# workshop-atmega8.net
KiCad netlist of a schematic drawn in EAGLE
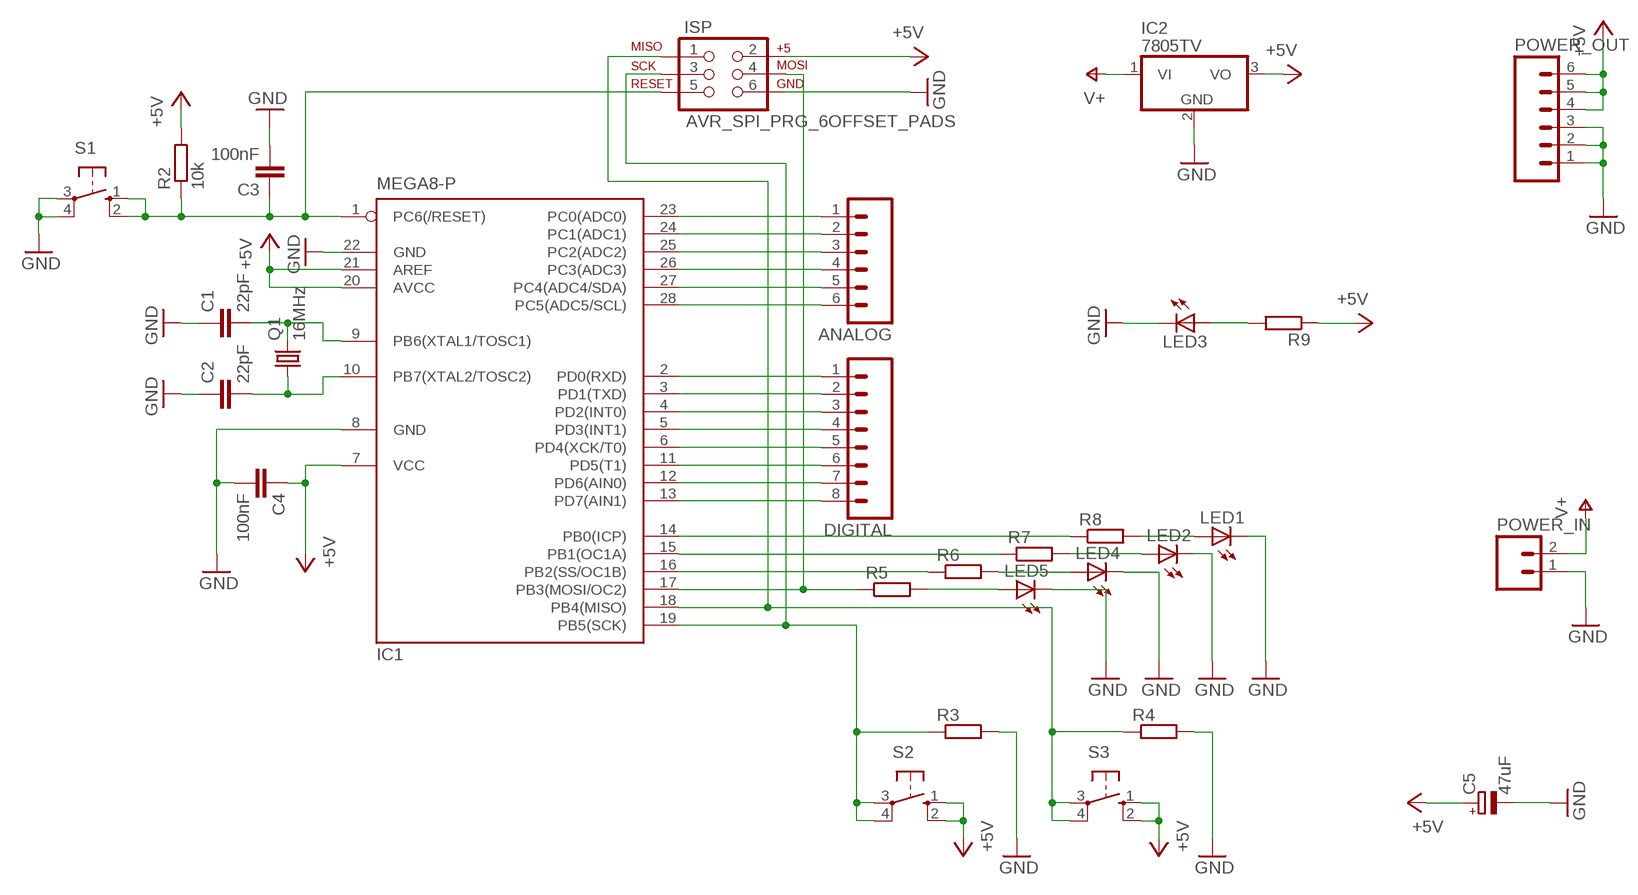
[diagram p0: schematic, sheet 1]

(export (version "E")
  (design (tool "Eeschema 10.0.6"))
  (components
    (comp (ref "ANALOG")
      (value "M06LOCK_LONGPADS")
      (footprint "eagle-import:1X06_LOCK_LONGPADS")
      (libsource (lib "eagle-import") (part "M06LOCK_LONGPADS"))
    )
    (comp (ref "C1")
      (value "22pF")
      (footprint "eagle-import:C025-025X050")
      (libsource (lib "eagle-import") (part "C-EU025-025X050"))
    )
    (comp (ref "C2")
      (value "22pF")
      (footprint "eagle-import:C025-025X050")
      (libsource (lib "eagle-import") (part "C-EU025-025X050"))
    )
    (comp (ref "C3")
      (value "100nF")
      (footprint "eagle-import:C025-025X050")
      (libsource (lib "eagle-import") (part "C-EU025-025X050"))
    )
    (comp (ref "C4")
      (value "100nF")
      (footprint "eagle-import:C025-025X050")
      (libsource (lib "eagle-import") (part "C-EU025-025X050"))
    )
    (comp (ref "C5")
      (value "47uF")
      (footprint "eagle-import:E2,5-7")
      (libsource (lib "eagle-import") (part "CPOL-EUE2.5-7"))
    )
    (comp (ref "DIGITAL")
      (value "M08LOCK_LONGPADS")
      (footprint "eagle-import:1X08_LOCK_LONGPADS")
      (libsource (lib "eagle-import") (part "M08LOCK_LONGPADS"))
    )
    (comp (ref "IC1")
      (value "MEGA8-P")
      (footprint "eagle-import:DIL28-3")
      (libsource (lib "eagle-import") (part "MEGA8-P"))
    )
    (comp (ref "IC2")
      (value "7805TV")
      (footprint "eagle-import:TO220V")
      (libsource (lib "eagle-import") (part "78TV05"))
    )
    (comp (ref "ISP")
      (value "AVR_SPI_PRG_6OFFSET_PADS")
      (footprint "eagle-import:2X3_OFFSET")
      (libsource (lib "eagle-import") (part "AVR_SPI_PRG_6OFFSET_PADS"))
    )
    (comp (ref "LED1")
      (value "LED5MM")
      (footprint "eagle-import:LED5MM")
      (libsource (lib "eagle-import") (part "LED5MM"))
    )
    (comp (ref "LED2")
      (value "LED5MM")
      (footprint "eagle-import:LED5MM")
      (libsource (lib "eagle-import") (part "LED5MM"))
    )
    (comp (ref "LED3")
      (value "LED5MM")
      (footprint "eagle-import:LED5MM")
      (libsource (lib "eagle-import") (part "LED5MM"))
    )
    (comp (ref "LED4")
      (value "LED5MM")
      (footprint "eagle-import:LED5MM")
      (libsource (lib "eagle-import") (part "LED5MM"))
    )
    (comp (ref "LED5")
      (value "LED5MM")
      (footprint "eagle-import:LED5MM")
      (libsource (lib "eagle-import") (part "LED5MM"))
    )
    (comp (ref "POWER_IN")
      (value "M02LOCK_LONGPADS")
      (footprint "eagle-import:1X02_LOCK_LONGPADS")
      (libsource (lib "eagle-import") (part "M02LOCK_LONGPADS"))
    )
    (comp (ref "POWER_OUT")
      (value "M06LOCK_LONGPADS")
      (footprint "eagle-import:1X06_LOCK_LONGPADS")
      (libsource (lib "eagle-import") (part "M06LOCK_LONGPADS"))
    )
    (comp (ref "Q1")
      (value "16MHz")
      (footprint "eagle-import:HC49_S")
      (libsource (lib "eagle-import") (part "CRYSTALHC49S"))
    )
    (comp (ref "R2")
      (value "10k")
      (footprint "eagle-import:0207_10")
      (libsource (lib "eagle-import") (part "R-EU_0207/10"))
    )
    (comp (ref "R3")
      (value "R-EU_0207/10")
      (footprint "eagle-import:0207_10")
      (libsource (lib "eagle-import") (part "R-EU_0207/10"))
    )
    (comp (ref "R4")
      (value "R-EU_0207/10")
      (footprint "eagle-import:0207_10")
      (libsource (lib "eagle-import") (part "R-EU_0207/10"))
    )
    (comp (ref "R5")
      (value "R-EU_0207/10")
      (footprint "eagle-import:0207_10")
      (libsource (lib "eagle-import") (part "R-EU_0207/10"))
    )
    (comp (ref "R6")
      (value "R-EU_0207/10")
      (footprint "eagle-import:0207_10")
      (libsource (lib "eagle-import") (part "R-EU_0207/10"))
    )
    (comp (ref "R7")
      (value "R-EU_0207/10")
      (footprint "eagle-import:0207_10")
      (libsource (lib "eagle-import") (part "R-EU_0207/10"))
    )
    (comp (ref "R8")
      (value "R-EU_0207/10")
      (footprint "eagle-import:0207_10")
      (libsource (lib "eagle-import") (part "R-EU_0207/10"))
    )
    (comp (ref "R9")
      (value "R-EU_0207/10")
      (footprint "eagle-import:0207_10")
      (libsource (lib "eagle-import") (part "R-EU_0207/10"))
    )
    (comp (ref "S1")
      (value "10-XX")
      (footprint "eagle-import:B3F-10XX")
      (fields (field (name "MPN") "B3F-1000"))
      (libsource (lib "eagle-import") (part "10-XX"))
    )
    (comp (ref "S2")
      (value "10-XX")
      (footprint "eagle-import:B3F-10XX")
      (fields (field (name "MPN") "B3F-1000"))
      (libsource (lib "eagle-import") (part "10-XX"))
    )
    (comp (ref "S3")
      (value "10-XX")
      (footprint "eagle-import:B3F-10XX")
      (fields (field (name "MPN") "B3F-1000"))
      (libsource (lib "eagle-import") (part "10-XX"))
    )
  )
  (nets
    (net (code "1") (name "+5V") (class "Default")
      (node (ref "C4") (pin "1") (pinfunction "1_1") (pintype "passive"))
      (node (ref "C5") (pin "+") (pinfunction "+_+") (pintype "passive"))
      (node (ref "IC1") (pin "20") (pinfunction "AVCC_20") (pintype "power_in"))
      (node (ref "IC1") (pin "21") (pinfunction "AREF_21") (pintype "passive"))
      (node (ref "IC1") (pin "7") (pinfunction "VCC_7") (pintype "power_in"))
      (node (ref "IC2") (pin "3") (pinfunction "VO_3") (pintype "passive"))
      (node (ref "ISP") (pin "2") (pinfunction "2_2") (pintype "passive"))
      (node (ref "POWER_OUT") (pin "4") (pinfunction "4_4") (pintype "passive"))
      (node (ref "POWER_OUT") (pin "5") (pinfunction "5_5") (pintype "passive"))
      (node (ref "POWER_OUT") (pin "6") (pinfunction "6_6") (pintype "passive"))
      (node (ref "R2") (pin "2") (pinfunction "2_2") (pintype "passive"))
      (node (ref "R9") (pin "1") (pinfunction "1_1") (pintype "passive"))
      (node (ref "S2") (pin "1") (pinfunction "S_1") (pintype "passive"))
      (node (ref "S2") (pin "2") (pinfunction "S1_2") (pintype "passive"))
      (node (ref "S3") (pin "1") (pinfunction "S_1") (pintype "passive"))
      (node (ref "S3") (pin "2") (pinfunction "S1_2") (pintype "passive"))
    )
    (net (code "2") (name "GND") (class "Default")
      (node (ref "C1") (pin "1") (pinfunction "1_1") (pintype "passive"))
      (node (ref "C2") (pin "1") (pinfunction "1_1") (pintype "passive"))
      (node (ref "C3") (pin "2") (pinfunction "2_2") (pintype "passive"))
      (node (ref "C4") (pin "2") (pinfunction "2_2") (pintype "passive"))
      (node (ref "C5") (pin "-") (pinfunction "-_-") (pintype "passive"))
      (node (ref "IC1") (pin "22") (pinfunction "GND_22") (pintype "power_in"))
      (node (ref "IC1") (pin "8") (pinfunction "GND_8") (pintype "power_in"))
      (node (ref "IC2") (pin "2") (pinfunction "GND_2") (pintype "passive"))
      (node (ref "ISP") (pin "6") (pinfunction "6_6") (pintype "passive"))
      (node (ref "LED1") (pin "K") (pinfunction "C_K") (pintype "passive"))
      (node (ref "LED2") (pin "K") (pinfunction "C_K") (pintype "passive"))
      (node (ref "LED3") (pin "K") (pinfunction "C_K") (pintype "passive"))
      (node (ref "LED4") (pin "K") (pinfunction "C_K") (pintype "passive"))
      (node (ref "LED5") (pin "K") (pinfunction "C_K") (pintype "passive"))
      (node (ref "POWER_IN") (pin "1") (pinfunction "1_1") (pintype "passive"))
      (node (ref "POWER_OUT") (pin "1") (pinfunction "1_1") (pintype "passive"))
      (node (ref "POWER_OUT") (pin "2") (pinfunction "2_2") (pintype "passive"))
      (node (ref "POWER_OUT") (pin "3") (pinfunction "3_3") (pintype "passive"))
      (node (ref "R3") (pin "2") (pinfunction "2_2") (pintype "passive"))
      (node (ref "R4") (pin "2") (pinfunction "2_2") (pintype "passive"))
      (node (ref "S1") (pin "3") (pinfunction "P_3") (pintype "passive"))
      (node (ref "S1") (pin "4") (pinfunction "P1_4") (pintype "passive"))
    )
    (net (code "3") (name "Net-(IC1-PB0(ICP))") (class "Default")
      (node (ref "IC1") (pin "14") (pinfunction "PB0(ICP)_14") (pintype "bidirectional"))
      (node (ref "R8") (pin "1") (pinfunction "1_1") (pintype "passive"))
    )
    (net (code "4") (name "Net-(IC1-PB1(OC1A))") (class "Default")
      (node (ref "IC1") (pin "15") (pinfunction "PB1(OC1A)_15") (pintype "bidirectional"))
      (node (ref "R7") (pin "1") (pinfunction "1_1") (pintype "passive"))
    )
    (net (code "5") (name "Net-(IC1-PB2(SS{slash}OC1B))") (class "Default")
      (node (ref "IC1") (pin "16") (pinfunction "PB2(SS/OC1B)_16") (pintype "bidirectional"))
      (node (ref "R6") (pin "1") (pinfunction "1_1") (pintype "passive"))
    )
    (net (code "6") (name "Net-(IC1-PB3(MOSI{slash}OC2))") (class "Default")
      (node (ref "IC1") (pin "17") (pinfunction "PB3(MOSI/OC2)_17") (pintype "bidirectional"))
      (node (ref "ISP") (pin "4") (pinfunction "4_4") (pintype "passive"))
      (node (ref "R5") (pin "1") (pinfunction "1_1") (pintype "passive"))
    )
    (net (code "7") (name "Net-(IC1-PB4(MISO))") (class "Default")
      (node (ref "IC1") (pin "18") (pinfunction "PB4(MISO)_18") (pintype "bidirectional"))
      (node (ref "ISP") (pin "1") (pinfunction "1_1") (pintype "passive"))
      (node (ref "R4") (pin "1") (pinfunction "1_1") (pintype "passive"))
      (node (ref "S3") (pin "3") (pinfunction "P_3") (pintype "passive"))
      (node (ref "S3") (pin "4") (pinfunction "P1_4") (pintype "passive"))
    )
    (net (code "8") (name "Net-(IC1-PB5(SCK))") (class "Default")
      (node (ref "IC1") (pin "19") (pinfunction "PB5(SCK)_19") (pintype "bidirectional"))
      (node (ref "ISP") (pin "3") (pinfunction "3_3") (pintype "passive"))
      (node (ref "R3") (pin "1") (pinfunction "1_1") (pintype "passive"))
      (node (ref "S2") (pin "3") (pinfunction "P_3") (pintype "passive"))
      (node (ref "S2") (pin "4") (pinfunction "P1_4") (pintype "passive"))
    )
    (net (code "9") (name "Net-(IC1-PB6(XTAL1{slash}TOSC1))") (class "Default")
      (node (ref "C1") (pin "2") (pinfunction "2_2") (pintype "passive"))
      (node (ref "IC1") (pin "9") (pinfunction "PB6(XTAL1/TOSC1)_9") (pintype "bidirectional"))
      (node (ref "Q1") (pin "2") (pinfunction "2_2") (pintype "passive"))
    )
    (net (code "10") (name "Net-(IC1-PB7(XTAL2{slash}TOSC2))") (class "Default")
      (node (ref "C2") (pin "2") (pinfunction "2_2") (pintype "passive"))
      (node (ref "IC1") (pin "10") (pinfunction "PB7(XTAL2/TOSC2)_10") (pintype "bidirectional"))
      (node (ref "Q1") (pin "1") (pinfunction "1_1") (pintype "passive"))
    )
    (net (code "11") (name "Net-(IC1-PC0(ADC0))") (class "Default")
      (node (ref "ANALOG") (pin "1") (pinfunction "1_1") (pintype "passive"))
      (node (ref "IC1") (pin "23") (pinfunction "PC0(ADC0)_23") (pintype "bidirectional"))
    )
    (net (code "12") (name "Net-(IC1-PC1(ADC1))") (class "Default")
      (node (ref "ANALOG") (pin "2") (pinfunction "2_2") (pintype "passive"))
      (node (ref "IC1") (pin "24") (pinfunction "PC1(ADC1)_24") (pintype "bidirectional"))
    )
    (net (code "13") (name "Net-(IC1-PC2(ADC2))") (class "Default")
      (node (ref "ANALOG") (pin "3") (pinfunction "3_3") (pintype "passive"))
      (node (ref "IC1") (pin "25") (pinfunction "PC2(ADC2)_25") (pintype "bidirectional"))
    )
    (net (code "14") (name "Net-(IC1-PC3(ADC3))") (class "Default")
      (node (ref "ANALOG") (pin "4") (pinfunction "4_4") (pintype "passive"))
      (node (ref "IC1") (pin "26") (pinfunction "PC3(ADC3)_26") (pintype "bidirectional"))
    )
    (net (code "15") (name "Net-(IC1-PC4(ADC4{slash}SDA))") (class "Default")
      (node (ref "ANALOG") (pin "5") (pinfunction "5_5") (pintype "passive"))
      (node (ref "IC1") (pin "27") (pinfunction "PC4(ADC4/SDA)_27") (pintype "bidirectional"))
    )
    (net (code "16") (name "Net-(IC1-PC5(ADC5{slash}SCL))") (class "Default")
      (node (ref "ANALOG") (pin "6") (pinfunction "6_6") (pintype "passive"))
      (node (ref "IC1") (pin "28") (pinfunction "PC5(ADC5/SCL)_28") (pintype "bidirectional"))
    )
    (net (code "17") (name "Net-(IC1-PC6({slash}RESET))") (class "Default")
      (node (ref "C3") (pin "1") (pinfunction "1_1") (pintype "passive"))
      (node (ref "IC1") (pin "1") (pinfunction "PC6(/RESET)_1") (pintype "bidirectional"))
      (node (ref "ISP") (pin "5") (pinfunction "5_5") (pintype "passive"))
      (node (ref "R2") (pin "1") (pinfunction "1_1") (pintype "passive"))
      (node (ref "S1") (pin "1") (pinfunction "S_1") (pintype "passive"))
      (node (ref "S1") (pin "2") (pinfunction "S1_2") (pintype "passive"))
    )
    (net (code "18") (name "Net-(IC1-PD0(RXD))") (class "Default")
      (node (ref "DIGITAL") (pin "1") (pinfunction "1_1") (pintype "passive"))
      (node (ref "IC1") (pin "2") (pinfunction "PD0(RXD)_2") (pintype "bidirectional"))
    )
    (net (code "19") (name "Net-(IC1-PD1(TXD))") (class "Default")
      (node (ref "DIGITAL") (pin "2") (pinfunction "2_2") (pintype "passive"))
      (node (ref "IC1") (pin "3") (pinfunction "PD1(TXD)_3") (pintype "bidirectional"))
    )
    (net (code "20") (name "Net-(IC1-PD2(INT0))") (class "Default")
      (node (ref "DIGITAL") (pin "3") (pinfunction "3_3") (pintype "passive"))
      (node (ref "IC1") (pin "4") (pinfunction "PD2(INT0)_4") (pintype "bidirectional"))
    )
    (net (code "21") (name "Net-(IC1-PD3(INT1))") (class "Default")
      (node (ref "DIGITAL") (pin "4") (pinfunction "4_4") (pintype "passive"))
      (node (ref "IC1") (pin "5") (pinfunction "PD3(INT1)_5") (pintype "bidirectional"))
    )
    (net (code "22") (name "Net-(IC1-PD4(XCK{slash}T0))") (class "Default")
      (node (ref "DIGITAL") (pin "5") (pinfunction "5_5") (pintype "passive"))
      (node (ref "IC1") (pin "6") (pinfunction "PD4(XCK/T0)_6") (pintype "bidirectional"))
    )
    (net (code "23") (name "Net-(IC1-PD5(T1))") (class "Default")
      (node (ref "DIGITAL") (pin "6") (pinfunction "6_6") (pintype "passive"))
      (node (ref "IC1") (pin "11") (pinfunction "PD5(T1)_11") (pintype "bidirectional"))
    )
    (net (code "24") (name "Net-(IC1-PD6(AIN0))") (class "Default")
      (node (ref "DIGITAL") (pin "7") (pinfunction "7_7") (pintype "passive"))
      (node (ref "IC1") (pin "12") (pinfunction "PD6(AIN0)_12") (pintype "bidirectional"))
    )
    (net (code "25") (name "Net-(IC1-PD7(AIN1))") (class "Default")
      (node (ref "DIGITAL") (pin "8") (pinfunction "8_8") (pintype "passive"))
      (node (ref "IC1") (pin "13") (pinfunction "PD7(AIN1)_13") (pintype "bidirectional"))
    )
    (net (code "26") (name "Net-(LED1-PadA)") (class "Default")
      (node (ref "LED1") (pin "A") (pinfunction "A_A") (pintype "passive"))
      (node (ref "R8") (pin "2") (pinfunction "2_2") (pintype "passive"))
    )
    (net (code "27") (name "Net-(LED2-PadA)") (class "Default")
      (node (ref "LED2") (pin "A") (pinfunction "A_A") (pintype "passive"))
      (node (ref "R7") (pin "2") (pinfunction "2_2") (pintype "passive"))
    )
    (net (code "28") (name "Net-(LED3-PadA)") (class "Default")
      (node (ref "LED3") (pin "A") (pinfunction "A_A") (pintype "passive"))
      (node (ref "R9") (pin "2") (pinfunction "2_2") (pintype "passive"))
    )
    (net (code "29") (name "Net-(LED4-PadA)") (class "Default")
      (node (ref "LED4") (pin "A") (pinfunction "A_A") (pintype "passive"))
      (node (ref "R6") (pin "2") (pinfunction "2_2") (pintype "passive"))
    )
    (net (code "30") (name "Net-(LED5-PadA)") (class "Default")
      (node (ref "LED5") (pin "A") (pinfunction "A_A") (pintype "passive"))
      (node (ref "R5") (pin "2") (pinfunction "2_2") (pintype "passive"))
    )
    (net (code "31") (name "V+") (class "Default")
      (node (ref "IC2") (pin "1") (pinfunction "VI_1") (pintype "input"))
      (node (ref "POWER_IN") (pin "2") (pinfunction "2_2") (pintype "passive"))
    )
  )
)
